# Power_Distribution_-_Power_Path_MOSFET.net
KiCad netlist of a schematic drawn in Altium Designer
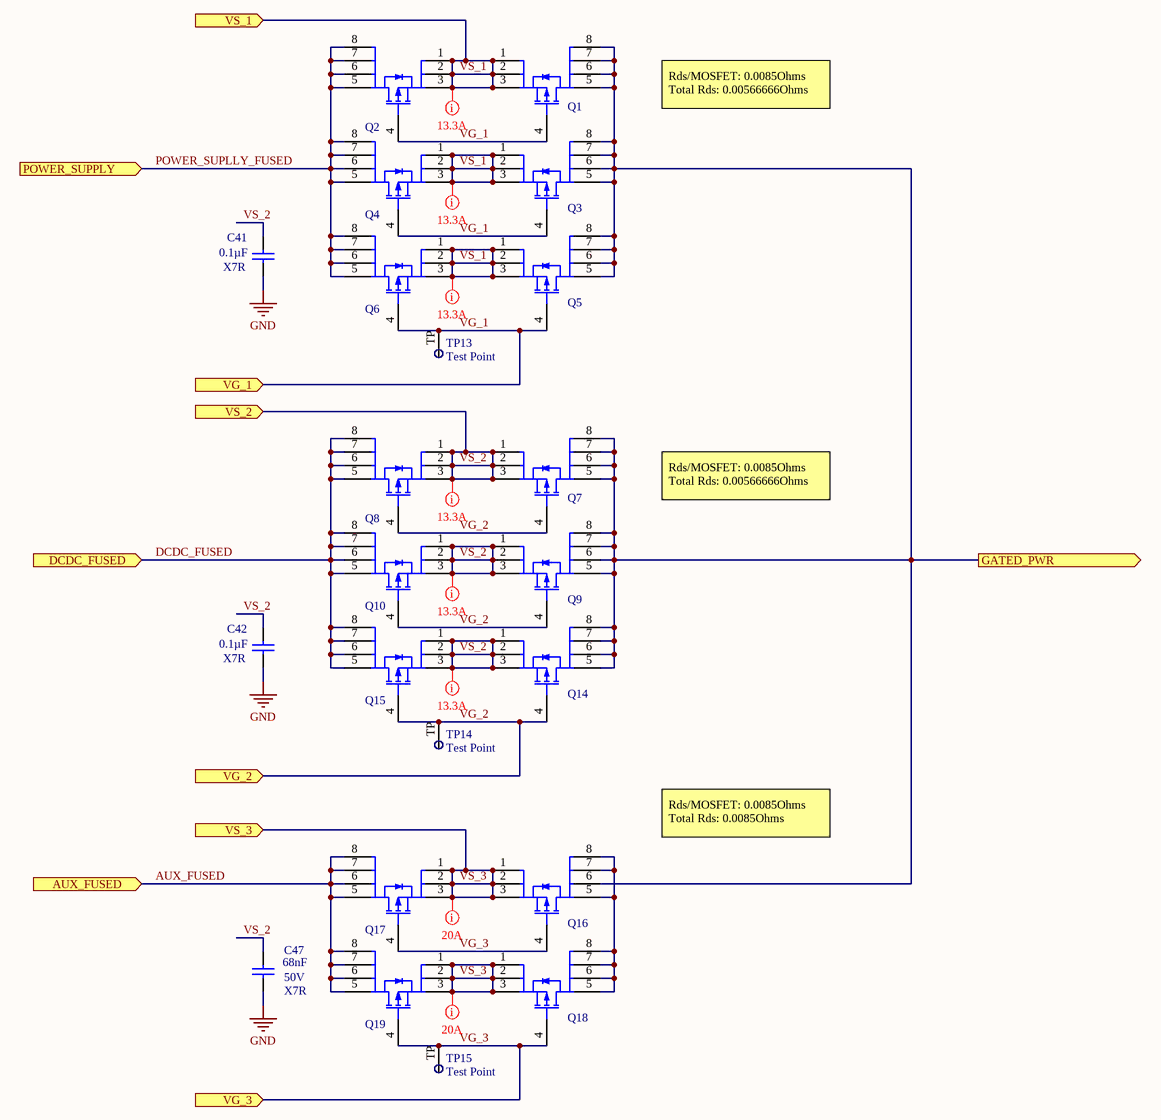
[diagram p0: Power Distribution - Power Path MOSFET.SchDoc]

(export (version "E")
  (design (tool "Eeschema 10.0.6"))
  (components
    (comp (ref "C41")
      (value "CAP CER 0.1UF 50V 10% X7R 0603")
      (footprint "CAP, 0603")
      (description "0.10µF ±10% 50V Ceramic Capacitor X7R 0603 (1608 Metric)")
      (fields
        (field (name "TOLERANCE") "±10%")
        (field (name "CAPACITANCE") "0.1µF")
        (field (name "TEMPERATURE COEFFICIENT") "X7R")
        (field (name "VOLTAGE") "50V")
      )
      (libsource (lib "Schematic Diagrams") (part "CAP CER 0.1UF 50V 10% X7R 0603"))
    )
    (comp (ref "C42")
      (value "CAP CER 0.1UF 50V 10% X7R 0603")
      (footprint "CAP, 0603")
      (description "0.10µF ±10% 50V Ceramic Capacitor X7R 0603 (1608 Metric)")
      (fields
        (field (name "TOLERANCE") "±10%")
        (field (name "CAPACITANCE") "0.1µF")
        (field (name "TEMPERATURE COEFFICIENT") "X7R")
        (field (name "VOLTAGE") "50V")
      )
      (libsource (lib "Schematic Diagrams") (part "CAP CER 0.1UF 50V 10% X7R 0603"))
    )
    (comp (ref "C47")
      (value "68nF")
      (footprint "CAP, 0603")
      (description "0.068µF 50V Ceramic Capacitor X7R 0603 (1608 Metric) 0.063\" L x 0.032\" W (1.60mm x 0.80mm)")
      (fields
        (field (name "MANUFACTURER") "Murata")
        (field (name "MANUFACTURER PART NUMBER") "GCM188R71H683KA57D")
        (field (name "VOLTAGE RATING") "50V")
        (field (name "DIELECTRIC") "X7R")
      )
      (libsource (lib "Schematic Diagrams") (part "CAP CER 0.068UF 10% 50V X7R 0603"))
    )
    (comp (ref "Q1")
      (value "MOSFET P-CH PWR56 40V 4.9 MOHM")
      (footprint "PMOS PWR56 40V 4.9 MOHM")
      (description "P-Channel 16V 2.5A (Ta) 650mW (Ta) Surface Mount X2-DFN2015-3")
      (libsource (lib "Schematic Diagrams") (part "MOSFET P-CH PWR56 40V 4.9 MOHM"))
    )
    (comp (ref "Q2")
      (value "MOSFET P-CH PWR56 40V 4.9 MOHM")
      (footprint "PMOS PWR56 40V 4.9 MOHM")
      (description "P-Channel 16V 2.5A (Ta) 650mW (Ta) Surface Mount X2-DFN2015-3")
      (libsource (lib "Schematic Diagrams") (part "MOSFET P-CH PWR56 40V 4.9 MOHM"))
    )
    (comp (ref "Q3")
      (value "MOSFET P-CH PWR56 40V 4.9 MOHM")
      (footprint "PMOS PWR56 40V 4.9 MOHM")
      (description "P-Channel 16V 2.5A (Ta) 650mW (Ta) Surface Mount X2-DFN2015-3")
      (libsource (lib "Schematic Diagrams") (part "MOSFET P-CH PWR56 40V 4.9 MOHM"))
    )
    (comp (ref "Q4")
      (value "MOSFET P-CH PWR56 40V 4.9 MOHM")
      (footprint "PMOS PWR56 40V 4.9 MOHM")
      (description "P-Channel 16V 2.5A (Ta) 650mW (Ta) Surface Mount X2-DFN2015-3")
      (libsource (lib "Schematic Diagrams") (part "MOSFET P-CH PWR56 40V 4.9 MOHM"))
    )
    (comp (ref "Q5")
      (value "MOSFET P-CH PWR56 40V 4.9 MOHM")
      (footprint "PMOS PWR56 40V 4.9 MOHM")
      (description "P-Channel 16V 2.5A (Ta) 650mW (Ta) Surface Mount X2-DFN2015-3")
      (libsource (lib "Schematic Diagrams") (part "MOSFET P-CH PWR56 40V 4.9 MOHM"))
    )
    (comp (ref "Q6")
      (value "MOSFET P-CH PWR56 40V 4.9 MOHM")
      (footprint "PMOS PWR56 40V 4.9 MOHM")
      (description "P-Channel 16V 2.5A (Ta) 650mW (Ta) Surface Mount X2-DFN2015-3")
      (libsource (lib "Schematic Diagrams") (part "MOSFET P-CH PWR56 40V 4.9 MOHM"))
    )
    (comp (ref "Q7")
      (value "MOSFET P-CH PWR56 40V 4.9 MOHM")
      (footprint "PMOS PWR56 40V 4.9 MOHM")
      (description "P-Channel 16V 2.5A (Ta) 650mW (Ta) Surface Mount X2-DFN2015-3")
      (libsource (lib "Schematic Diagrams") (part "MOSFET P-CH PWR56 40V 4.9 MOHM"))
    )
    (comp (ref "Q8")
      (value "MOSFET P-CH PWR56 40V 4.9 MOHM")
      (footprint "PMOS PWR56 40V 4.9 MOHM")
      (description "P-Channel 16V 2.5A (Ta) 650mW (Ta) Surface Mount X2-DFN2015-3")
      (libsource (lib "Schematic Diagrams") (part "MOSFET P-CH PWR56 40V 4.9 MOHM"))
    )
    (comp (ref "Q9")
      (value "MOSFET P-CH PWR56 40V 4.9 MOHM")
      (footprint "PMOS PWR56 40V 4.9 MOHM")
      (description "P-Channel 16V 2.5A (Ta) 650mW (Ta) Surface Mount X2-DFN2015-3")
      (libsource (lib "Schematic Diagrams") (part "MOSFET P-CH PWR56 40V 4.9 MOHM"))
    )
    (comp (ref "Q10")
      (value "MOSFET P-CH PWR56 40V 4.9 MOHM")
      (footprint "PMOS PWR56 40V 4.9 MOHM")
      (description "P-Channel 16V 2.5A (Ta) 650mW (Ta) Surface Mount X2-DFN2015-3")
      (libsource (lib "Schematic Diagrams") (part "MOSFET P-CH PWR56 40V 4.9 MOHM"))
    )
    (comp (ref "Q14")
      (value "MOSFET P-CH PWR56 40V 4.9 MOHM")
      (footprint "PMOS PWR56 40V 4.9 MOHM")
      (description "P-Channel 16V 2.5A (Ta) 650mW (Ta) Surface Mount X2-DFN2015-3")
      (libsource (lib "Schematic Diagrams") (part "MOSFET P-CH PWR56 40V 4.9 MOHM"))
    )
    (comp (ref "Q15")
      (value "MOSFET P-CH PWR56 40V 4.9 MOHM")
      (footprint "PMOS PWR56 40V 4.9 MOHM")
      (description "P-Channel 16V 2.5A (Ta) 650mW (Ta) Surface Mount X2-DFN2015-3")
      (libsource (lib "Schematic Diagrams") (part "MOSFET P-CH PWR56 40V 4.9 MOHM"))
    )
    (comp (ref "Q16")
      (value "MOSFET P-CH PWR56 40V 4.9 MOHM")
      (footprint "PMOS PWR56 40V 4.9 MOHM")
      (description "P-Channel 16V 2.5A (Ta) 650mW (Ta) Surface Mount X2-DFN2015-3")
      (libsource (lib "Schematic Diagrams") (part "MOSFET P-CH PWR56 40V 4.9 MOHM"))
    )
    (comp (ref "Q17")
      (value "MOSFET P-CH PWR56 40V 4.9 MOHM")
      (footprint "PMOS PWR56 40V 4.9 MOHM")
      (description "P-Channel 16V 2.5A (Ta) 650mW (Ta) Surface Mount X2-DFN2015-3")
      (libsource (lib "Schematic Diagrams") (part "MOSFET P-CH PWR56 40V 4.9 MOHM"))
    )
    (comp (ref "Q18")
      (value "MOSFET P-CH PWR56 40V 4.9 MOHM")
      (footprint "PMOS PWR56 40V 4.9 MOHM")
      (description "P-Channel 16V 2.5A (Ta) 650mW (Ta) Surface Mount X2-DFN2015-3")
      (libsource (lib "Schematic Diagrams") (part "MOSFET P-CH PWR56 40V 4.9 MOHM"))
    )
    (comp (ref "Q19")
      (value "MOSFET P-CH PWR56 40V 4.9 MOHM")
      (footprint "PMOS PWR56 40V 4.9 MOHM")
      (description "P-Channel 16V 2.5A (Ta) 650mW (Ta) Surface Mount X2-DFN2015-3")
      (libsource (lib "Schematic Diagrams") (part "MOSFET P-CH PWR56 40V 4.9 MOHM"))
    )
    (comp (ref "TP13")
      (value "Test Point")
      (footprint "Test Point")
      (libsource (lib "Schematic Diagrams") (part "Test Point"))
    )
    (comp (ref "TP14")
      (value "Test Point")
      (footprint "Test Point")
      (libsource (lib "Schematic Diagrams") (part "Test Point"))
    )
    (comp (ref "TP15")
      (value "Test Point")
      (footprint "Test Point")
      (libsource (lib "Schematic Diagrams") (part "Test Point"))
    )
  )
  (nets
    (net (code "1") (name "/AUX_FUSED") (class "Default")
      (node (ref "Q17") (pin "5") (pinfunction "D_5") (pintype "passive"))
      (node (ref "Q17") (pin "6") (pinfunction "D_6") (pintype "passive"))
      (node (ref "Q17") (pin "7") (pinfunction "D_7") (pintype "passive"))
      (node (ref "Q17") (pin "8") (pinfunction "D_8") (pintype "passive"))
      (node (ref "Q19") (pin "5") (pinfunction "D_5") (pintype "passive"))
      (node (ref "Q19") (pin "6") (pinfunction "D_6") (pintype "passive"))
      (node (ref "Q19") (pin "7") (pinfunction "D_7") (pintype "passive"))
      (node (ref "Q19") (pin "8") (pinfunction "D_8") (pintype "passive"))
    )
    (net (code "2") (name "/DCDC_FUSED") (class "Default")
      (node (ref "Q10") (pin "5") (pinfunction "D_5") (pintype "passive"))
      (node (ref "Q10") (pin "6") (pinfunction "D_6") (pintype "passive"))
      (node (ref "Q10") (pin "7") (pinfunction "D_7") (pintype "passive"))
      (node (ref "Q10") (pin "8") (pinfunction "D_8") (pintype "passive"))
      (node (ref "Q15") (pin "5") (pinfunction "D_5") (pintype "passive"))
      (node (ref "Q15") (pin "6") (pinfunction "D_6") (pintype "passive"))
      (node (ref "Q15") (pin "7") (pinfunction "D_7") (pintype "passive"))
      (node (ref "Q15") (pin "8") (pinfunction "D_8") (pintype "passive"))
      (node (ref "Q8") (pin "5") (pinfunction "D_5") (pintype "passive"))
      (node (ref "Q8") (pin "6") (pinfunction "D_6") (pintype "passive"))
      (node (ref "Q8") (pin "7") (pinfunction "D_7") (pintype "passive"))
      (node (ref "Q8") (pin "8") (pinfunction "D_8") (pintype "passive"))
    )
    (net (code "3") (name "/GATED_PWR") (class "Default")
      (node (ref "Q1") (pin "5") (pinfunction "D_5") (pintype "passive"))
      (node (ref "Q1") (pin "6") (pinfunction "D_6") (pintype "passive"))
      (node (ref "Q1") (pin "7") (pinfunction "D_7") (pintype "passive"))
      (node (ref "Q1") (pin "8") (pinfunction "D_8") (pintype "passive"))
      (node (ref "Q14") (pin "5") (pinfunction "D_5") (pintype "passive"))
      (node (ref "Q14") (pin "6") (pinfunction "D_6") (pintype "passive"))
      (node (ref "Q14") (pin "7") (pinfunction "D_7") (pintype "passive"))
      (node (ref "Q14") (pin "8") (pinfunction "D_8") (pintype "passive"))
      (node (ref "Q16") (pin "6") (pinfunction "D_6") (pintype "passive"))
      (node (ref "Q3") (pin "5") (pinfunction "D_5") (pintype "passive"))
      (node (ref "Q3") (pin "6") (pinfunction "D_6") (pintype "passive"))
      (node (ref "Q3") (pin "7") (pinfunction "D_7") (pintype "passive"))
      (node (ref "Q3") (pin "8") (pinfunction "D_8") (pintype "passive"))
      (node (ref "Q5") (pin "5") (pinfunction "D_5") (pintype "passive"))
      (node (ref "Q5") (pin "6") (pinfunction "D_6") (pintype "passive"))
      (node (ref "Q5") (pin "7") (pinfunction "D_7") (pintype "passive"))
      (node (ref "Q5") (pin "8") (pinfunction "D_8") (pintype "passive"))
      (node (ref "Q7") (pin "5") (pinfunction "D_5") (pintype "passive"))
      (node (ref "Q7") (pin "6") (pinfunction "D_6") (pintype "passive"))
      (node (ref "Q7") (pin "7") (pinfunction "D_7") (pintype "passive"))
      (node (ref "Q7") (pin "8") (pinfunction "D_8") (pintype "passive"))
      (node (ref "Q9") (pin "5") (pinfunction "D_5") (pintype "passive"))
      (node (ref "Q9") (pin "6") (pinfunction "D_6") (pintype "passive"))
      (node (ref "Q9") (pin "7") (pinfunction "D_7") (pintype "passive"))
      (node (ref "Q9") (pin "8") (pinfunction "D_8") (pintype "passive"))
    )
    (net (code "4") (name "/POWER_SUPLLY_FUSED") (class "Default")
      (node (ref "Q2") (pin "5") (pinfunction "D_5") (pintype "passive"))
      (node (ref "Q2") (pin "6") (pinfunction "D_6") (pintype "passive"))
      (node (ref "Q2") (pin "7") (pinfunction "D_7") (pintype "passive"))
      (node (ref "Q2") (pin "8") (pinfunction "D_8") (pintype "passive"))
      (node (ref "Q4") (pin "5") (pinfunction "D_5") (pintype "passive"))
      (node (ref "Q4") (pin "6") (pinfunction "D_6") (pintype "passive"))
      (node (ref "Q4") (pin "7") (pinfunction "D_7") (pintype "passive"))
      (node (ref "Q4") (pin "8") (pinfunction "D_8") (pintype "passive"))
      (node (ref "Q6") (pin "5") (pinfunction "D_5") (pintype "passive"))
      (node (ref "Q6") (pin "6") (pinfunction "D_6") (pintype "passive"))
      (node (ref "Q6") (pin "7") (pinfunction "D_7") (pintype "passive"))
      (node (ref "Q6") (pin "8") (pinfunction "D_8") (pintype "passive"))
    )
    (net (code "5") (name "/VG_1") (class "Default")
      (node (ref "Q1") (pin "4") (pinfunction "G_4") (pintype "passive"))
      (node (ref "Q2") (pin "4") (pinfunction "G_4") (pintype "passive"))
      (node (ref "Q3") (pin "4") (pinfunction "G_4") (pintype "passive"))
      (node (ref "Q4") (pin "4") (pinfunction "G_4") (pintype "passive"))
      (node (ref "Q5") (pin "4") (pinfunction "G_4") (pintype "passive"))
      (node (ref "Q6") (pin "4") (pinfunction "G_4") (pintype "passive"))
      (node (ref "TP13") (pin "TP") (pinfunction "1_TP") (pintype "passive"))
    )
    (net (code "6") (name "/VG_2") (class "Default")
      (node (ref "Q10") (pin "4") (pinfunction "G_4") (pintype "passive"))
      (node (ref "Q14") (pin "4") (pinfunction "G_4") (pintype "passive"))
      (node (ref "Q15") (pin "4") (pinfunction "G_4") (pintype "passive"))
      (node (ref "Q7") (pin "4") (pinfunction "G_4") (pintype "passive"))
      (node (ref "Q8") (pin "4") (pinfunction "G_4") (pintype "passive"))
      (node (ref "Q9") (pin "4") (pinfunction "G_4") (pintype "passive"))
      (node (ref "TP14") (pin "TP") (pinfunction "1_TP") (pintype "passive"))
    )
    (net (code "7") (name "/VG_3") (class "Default")
      (node (ref "Q16") (pin "4") (pinfunction "G_4") (pintype "passive"))
      (node (ref "Q17") (pin "4") (pinfunction "G_4") (pintype "passive"))
      (node (ref "Q18") (pin "4") (pinfunction "G_4") (pintype "passive"))
      (node (ref "Q19") (pin "4") (pinfunction "G_4") (pintype "passive"))
      (node (ref "TP15") (pin "TP") (pinfunction "1_TP") (pintype "passive"))
    )
    (net (code "8") (name "/VS_1") (class "Default")
      (node (ref "Q1") (pin "1") (pinfunction "S_1") (pintype "passive"))
      (node (ref "Q1") (pin "2") (pinfunction "S_2") (pintype "passive"))
      (node (ref "Q1") (pin "3") (pinfunction "S_3") (pintype "passive"))
      (node (ref "Q2") (pin "1") (pinfunction "S_1") (pintype "passive"))
      (node (ref "Q2") (pin "2") (pinfunction "S_2") (pintype "passive"))
      (node (ref "Q2") (pin "3") (pinfunction "S_3") (pintype "passive"))
      (node (ref "Q3") (pin "1") (pinfunction "S_1") (pintype "passive"))
      (node (ref "Q3") (pin "2") (pinfunction "S_2") (pintype "passive"))
      (node (ref "Q3") (pin "3") (pinfunction "S_3") (pintype "passive"))
      (node (ref "Q4") (pin "1") (pinfunction "S_1") (pintype "passive"))
      (node (ref "Q4") (pin "2") (pinfunction "S_2") (pintype "passive"))
      (node (ref "Q4") (pin "3") (pinfunction "S_3") (pintype "passive"))
      (node (ref "Q5") (pin "1") (pinfunction "S_1") (pintype "passive"))
      (node (ref "Q5") (pin "2") (pinfunction "S_2") (pintype "passive"))
      (node (ref "Q5") (pin "3") (pinfunction "S_3") (pintype "passive"))
      (node (ref "Q6") (pin "1") (pinfunction "S_1") (pintype "passive"))
      (node (ref "Q6") (pin "2") (pinfunction "S_2") (pintype "passive"))
      (node (ref "Q6") (pin "3") (pinfunction "S_3") (pintype "passive"))
    )
    (net (code "9") (name "/VS_2") (class "Default")
      (node (ref "C41") (pin "1") (pinfunction "1_1") (pintype "passive"))
      (node (ref "C42") (pin "1") (pinfunction "1_1") (pintype "passive"))
      (node (ref "C47") (pin "1") (pinfunction "1_1") (pintype "passive"))
      (node (ref "Q10") (pin "1") (pinfunction "S_1") (pintype "passive"))
      (node (ref "Q10") (pin "2") (pinfunction "S_2") (pintype "passive"))
      (node (ref "Q10") (pin "3") (pinfunction "S_3") (pintype "passive"))
      (node (ref "Q14") (pin "1") (pinfunction "S_1") (pintype "passive"))
      (node (ref "Q14") (pin "2") (pinfunction "S_2") (pintype "passive"))
      (node (ref "Q14") (pin "3") (pinfunction "S_3") (pintype "passive"))
      (node (ref "Q15") (pin "1") (pinfunction "S_1") (pintype "passive"))
      (node (ref "Q15") (pin "2") (pinfunction "S_2") (pintype "passive"))
      (node (ref "Q15") (pin "3") (pinfunction "S_3") (pintype "passive"))
      (node (ref "Q7") (pin "1") (pinfunction "S_1") (pintype "passive"))
      (node (ref "Q7") (pin "2") (pinfunction "S_2") (pintype "passive"))
      (node (ref "Q7") (pin "3") (pinfunction "S_3") (pintype "passive"))
      (node (ref "Q8") (pin "1") (pinfunction "S_1") (pintype "passive"))
      (node (ref "Q8") (pin "2") (pinfunction "S_2") (pintype "passive"))
      (node (ref "Q8") (pin "3") (pinfunction "S_3") (pintype "passive"))
      (node (ref "Q9") (pin "1") (pinfunction "S_1") (pintype "passive"))
      (node (ref "Q9") (pin "2") (pinfunction "S_2") (pintype "passive"))
      (node (ref "Q9") (pin "3") (pinfunction "S_3") (pintype "passive"))
    )
    (net (code "10") (name "/VS_3") (class "Default")
      (node (ref "Q16") (pin "1") (pinfunction "S_1") (pintype "passive"))
      (node (ref "Q16") (pin "2") (pinfunction "S_2") (pintype "passive"))
      (node (ref "Q16") (pin "3") (pinfunction "S_3") (pintype "passive"))
      (node (ref "Q17") (pin "1") (pinfunction "S_1") (pintype "passive"))
      (node (ref "Q17") (pin "2") (pinfunction "S_2") (pintype "passive"))
      (node (ref "Q17") (pin "3") (pinfunction "S_3") (pintype "passive"))
      (node (ref "Q18") (pin "1") (pinfunction "S_1") (pintype "passive"))
      (node (ref "Q18") (pin "2") (pinfunction "S_2") (pintype "passive"))
      (node (ref "Q18") (pin "3") (pinfunction "S_3") (pintype "passive"))
      (node (ref "Q19") (pin "1") (pinfunction "S_1") (pintype "passive"))
      (node (ref "Q19") (pin "2") (pinfunction "S_2") (pintype "passive"))
      (node (ref "Q19") (pin "3") (pinfunction "S_3") (pintype "passive"))
    )
    (net (code "11") (name "GND") (class "Default")
      (node (ref "C41") (pin "2") (pinfunction "2_2") (pintype "passive"))
      (node (ref "C42") (pin "2") (pinfunction "2_2") (pintype "passive"))
      (node (ref "C47") (pin "2") (pinfunction "2_2") (pintype "passive"))
    )
    (net (code "12") (name "Net-(Q16-D-Pad5)") (class "Default")
      (node (ref "Q16") (pin "5") (pinfunction "D_5") (pintype "passive"))
      (node (ref "Q16") (pin "7") (pinfunction "D_7") (pintype "passive"))
      (node (ref "Q16") (pin "8") (pinfunction "D_8") (pintype "passive"))
      (node (ref "Q18") (pin "5") (pinfunction "D_5") (pintype "passive"))
      (node (ref "Q18") (pin "6") (pinfunction "D_6") (pintype "passive"))
      (node (ref "Q18") (pin "7") (pinfunction "D_7") (pintype "passive"))
      (node (ref "Q18") (pin "8") (pinfunction "D_8") (pintype "passive"))
    )
  )
)
